# tqfp-sandwich-blank.net
KiCad netlist of a schematic drawn in EAGLE
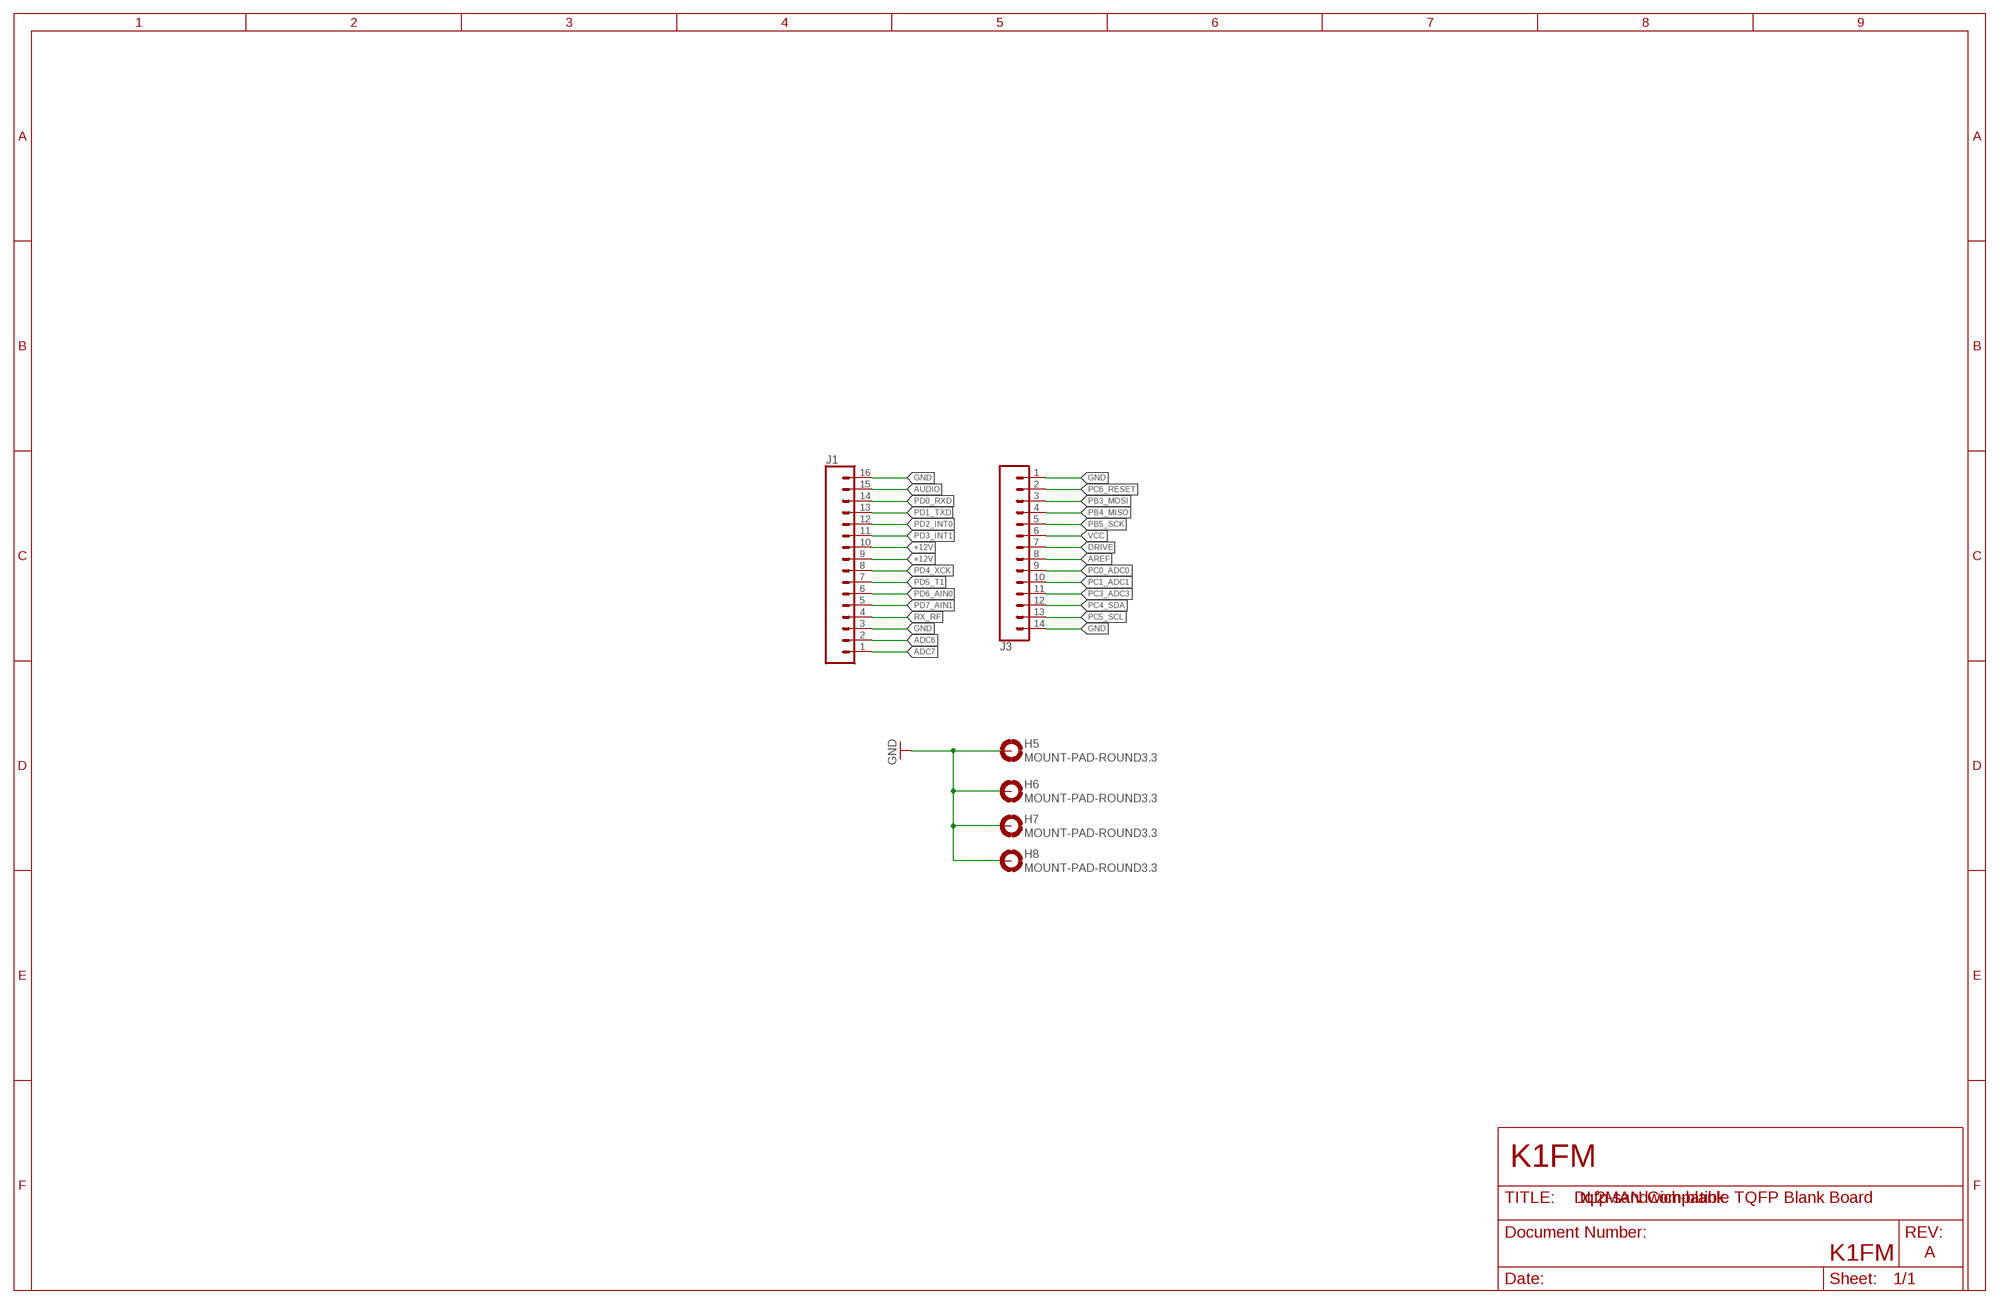
[diagram p0: schematic, sheet 1]

(export (version "E")
  (design (tool "Eeschema 10.0.6"))
  (components
    (comp (ref "H5")
      (value "MOUNT-PAD-ROUND3.3")
      (footprint "eagle-import:3,3-PAD")
      (libsource (lib "eagle-import") (part "MOUNT-PAD-ROUND3.3"))
    )
    (comp (ref "H6")
      (value "MOUNT-PAD-ROUND3.3")
      (footprint "eagle-import:3,3-PAD")
      (libsource (lib "eagle-import") (part "MOUNT-PAD-ROUND3.3"))
    )
    (comp (ref "H7")
      (value "MOUNT-PAD-ROUND3.3")
      (footprint "eagle-import:3,3-PAD")
      (libsource (lib "eagle-import") (part "MOUNT-PAD-ROUND3.3"))
    )
    (comp (ref "H8")
      (value "MOUNT-PAD-ROUND3.3")
      (footprint "eagle-import:3,3-PAD")
      (libsource (lib "eagle-import") (part "MOUNT-PAD-ROUND3.3"))
    )
    (comp (ref "J1")
      (value "CONN_16")
      (footprint "eagle-import:1X16")
      (libsource (lib "eagle-import") (part "CONN_16"))
    )
    (comp (ref "J3")
      (value "CONN_14")
      (footprint "eagle-import:1X14")
      (libsource (lib "eagle-import") (part "CONN_14"))
    )
  )
  (nets
    (net (code "1") (name "+12V") (class "Default")
      (node (ref "J1") (pin "10") (pinfunction "10_10") (pintype "passive"))
      (node (ref "J1") (pin "9") (pinfunction "9_9") (pintype "passive"))
    )
    (net (code "2") (name "ADC6") (class "Default")
      (node (ref "J1") (pin "2") (pinfunction "2_2") (pintype "passive"))
    )
    (net (code "3") (name "ADC7") (class "Default")
      (node (ref "J1") (pin "1") (pinfunction "1_1") (pintype "passive"))
    )
    (net (code "4") (name "AREF") (class "Default")
      (node (ref "J3") (pin "8") (pinfunction "8_8") (pintype "passive"))
    )
    (net (code "5") (name "AUDIO") (class "Default")
      (node (ref "J1") (pin "15") (pinfunction "15_15") (pintype "passive"))
    )
    (net (code "6") (name "DRIVE") (class "Default")
      (node (ref "J3") (pin "7") (pinfunction "7_7") (pintype "passive"))
    )
    (net (code "7") (name "GND") (class "Default")
      (node (ref "H5") (pin "B3,3") (pinfunction "MOUNT_B3,3") (pintype "passive"))
      (node (ref "H6") (pin "B3,3") (pinfunction "MOUNT_B3,3") (pintype "passive"))
      (node (ref "H7") (pin "B3,3") (pinfunction "MOUNT_B3,3") (pintype "passive"))
      (node (ref "H8") (pin "B3,3") (pinfunction "MOUNT_B3,3") (pintype "passive"))
      (node (ref "J1") (pin "16") (pinfunction "16_16") (pintype "passive"))
      (node (ref "J1") (pin "3") (pinfunction "3_3") (pintype "passive"))
      (node (ref "J3") (pin "1") (pinfunction "1_1") (pintype "passive"))
      (node (ref "J3") (pin "14") (pinfunction "14_14") (pintype "passive"))
    )
    (net (code "8") (name "PB3_MOSI") (class "Default")
      (node (ref "J3") (pin "3") (pinfunction "3_3") (pintype "passive"))
    )
    (net (code "9") (name "PB4_MISO") (class "Default")
      (node (ref "J3") (pin "4") (pinfunction "4_4") (pintype "passive"))
    )
    (net (code "10") (name "PB5_SCK") (class "Default")
      (node (ref "J3") (pin "5") (pinfunction "5_5") (pintype "passive"))
    )
    (net (code "11") (name "PC0_ADC0") (class "Default")
      (node (ref "J3") (pin "9") (pinfunction "9_9") (pintype "passive"))
    )
    (net (code "12") (name "PC1_ADC1") (class "Default")
      (node (ref "J3") (pin "10") (pinfunction "10_10") (pintype "passive"))
    )
    (net (code "13") (name "PC3_ADC3") (class "Default")
      (node (ref "J3") (pin "11") (pinfunction "11_11") (pintype "passive"))
    )
    (net (code "14") (name "PC4_SDA") (class "Default")
      (node (ref "J3") (pin "12") (pinfunction "12_12") (pintype "passive"))
    )
    (net (code "15") (name "PC5_SCL") (class "Default")
      (node (ref "J3") (pin "13") (pinfunction "13_13") (pintype "passive"))
    )
    (net (code "16") (name "PC6_RESET") (class "Default")
      (node (ref "J3") (pin "2") (pinfunction "2_2") (pintype "passive"))
    )
    (net (code "17") (name "PD0_RXD") (class "Default")
      (node (ref "J1") (pin "14") (pinfunction "14_14") (pintype "passive"))
    )
    (net (code "18") (name "PD1_TXD") (class "Default")
      (node (ref "J1") (pin "13") (pinfunction "13_13") (pintype "passive"))
    )
    (net (code "19") (name "PD2_INT0") (class "Default")
      (node (ref "J1") (pin "12") (pinfunction "12_12") (pintype "passive"))
    )
    (net (code "20") (name "PD3_INT1") (class "Default")
      (node (ref "J1") (pin "11") (pinfunction "11_11") (pintype "passive"))
    )
    (net (code "21") (name "PD4_XCK") (class "Default")
      (node (ref "J1") (pin "8") (pinfunction "8_8") (pintype "passive"))
    )
    (net (code "22") (name "PD5_T1") (class "Default")
      (node (ref "J1") (pin "7") (pinfunction "7_7") (pintype "passive"))
    )
    (net (code "23") (name "PD6_AIN0") (class "Default")
      (node (ref "J1") (pin "6") (pinfunction "6_6") (pintype "passive"))
    )
    (net (code "24") (name "PD7_AIN1") (class "Default")
      (node (ref "J1") (pin "5") (pinfunction "5_5") (pintype "passive"))
    )
    (net (code "25") (name "RX_RF") (class "Default")
      (node (ref "J1") (pin "4") (pinfunction "4_4") (pintype "passive"))
    )
    (net (code "26") (name "VCC") (class "Default")
      (node (ref "J3") (pin "6") (pinfunction "6_6") (pintype "passive"))
    )
  )
)
